# POWER_OUT.net
KiCad netlist of a schematic drawn in Altium Designer
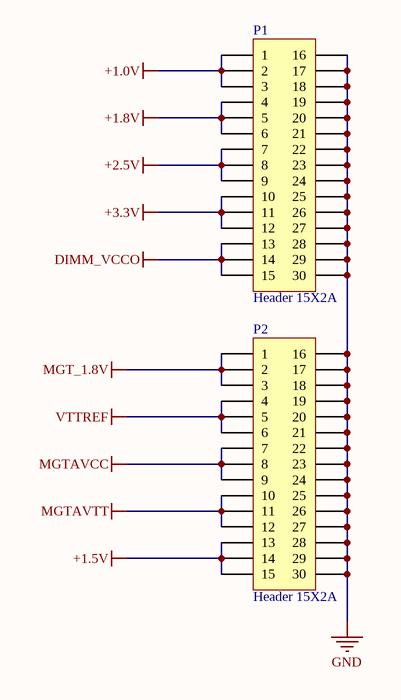
[diagram p0: POWER_OUT.SchDoc]

(export (version "E")
  (design (tool "Eeschema 10.0.6"))
  (components
    (comp (ref "P1")
      (value "Header 15X2A")
      (footprint "HDR2X15_CEN")
      (description "Header, 15-Pin, Dual row")
      (fields (field (name "PUBLISHER") "Altium Limited"))
      (libsource (lib "Miscellaneous Connectors") (part "Header 15X2A"))
    )
    (comp (ref "P2")
      (value "Header 15X2A")
      (footprint "HDR2X15_CEN")
      (description "Header, 15-Pin, Dual row")
      (fields (field (name "PUBLISHER") "Altium Limited"))
      (libsource (lib "Miscellaneous Connectors") (part "Header 15X2A"))
    )
  )
  (nets
    (net (code "1") (name "+1.0V") (class "Default")
      (node (ref "P1") (pin "1") (pinfunction "1_1") (pintype "passive"))
      (node (ref "P1") (pin "2") (pinfunction "2_2") (pintype "passive"))
      (node (ref "P1") (pin "3") (pinfunction "3_3") (pintype "passive"))
    )
    (net (code "2") (name "+1.5V") (class "Default")
      (node (ref "P2") (pin "13") (pinfunction "13_13") (pintype "passive"))
      (node (ref "P2") (pin "14") (pinfunction "14_14") (pintype "passive"))
      (node (ref "P2") (pin "15") (pinfunction "15_15") (pintype "passive"))
    )
    (net (code "3") (name "+1.8V") (class "Default")
      (node (ref "P1") (pin "4") (pinfunction "4_4") (pintype "passive"))
      (node (ref "P1") (pin "5") (pinfunction "5_5") (pintype "passive"))
      (node (ref "P1") (pin "6") (pinfunction "6_6") (pintype "passive"))
    )
    (net (code "4") (name "+2.5V") (class "Default")
      (node (ref "P1") (pin "7") (pinfunction "7_7") (pintype "passive"))
      (node (ref "P1") (pin "8") (pinfunction "8_8") (pintype "passive"))
      (node (ref "P1") (pin "9") (pinfunction "9_9") (pintype "passive"))
    )
    (net (code "5") (name "+3.3V") (class "Default")
      (node (ref "P1") (pin "10") (pinfunction "10_10") (pintype "passive"))
      (node (ref "P1") (pin "11") (pinfunction "11_11") (pintype "passive"))
      (node (ref "P1") (pin "12") (pinfunction "12_12") (pintype "passive"))
    )
    (net (code "6") (name "DIMM_VCCO") (class "Default")
      (node (ref "P1") (pin "13") (pinfunction "13_13") (pintype "passive"))
      (node (ref "P1") (pin "14") (pinfunction "14_14") (pintype "passive"))
      (node (ref "P1") (pin "15") (pinfunction "15_15") (pintype "passive"))
    )
    (net (code "7") (name "GND") (class "Default")
      (node (ref "P1") (pin "16") (pinfunction "16_16") (pintype "passive"))
      (node (ref "P1") (pin "17") (pinfunction "17_17") (pintype "passive"))
      (node (ref "P1") (pin "18") (pinfunction "18_18") (pintype "passive"))
      (node (ref "P1") (pin "19") (pinfunction "19_19") (pintype "passive"))
      (node (ref "P1") (pin "20") (pinfunction "20_20") (pintype "passive"))
      (node (ref "P1") (pin "21") (pinfunction "21_21") (pintype "passive"))
      (node (ref "P1") (pin "22") (pinfunction "22_22") (pintype "passive"))
      (node (ref "P1") (pin "23") (pinfunction "23_23") (pintype "passive"))
      (node (ref "P1") (pin "24") (pinfunction "24_24") (pintype "passive"))
      (node (ref "P1") (pin "25") (pinfunction "25_25") (pintype "passive"))
      (node (ref "P1") (pin "26") (pinfunction "26_26") (pintype "passive"))
      (node (ref "P1") (pin "27") (pinfunction "27_27") (pintype "passive"))
      (node (ref "P1") (pin "28") (pinfunction "28_28") (pintype "passive"))
      (node (ref "P1") (pin "29") (pinfunction "29_29") (pintype "passive"))
      (node (ref "P1") (pin "30") (pinfunction "30_30") (pintype "passive"))
      (node (ref "P2") (pin "16") (pinfunction "16_16") (pintype "passive"))
      (node (ref "P2") (pin "17") (pinfunction "17_17") (pintype "passive"))
      (node (ref "P2") (pin "18") (pinfunction "18_18") (pintype "passive"))
      (node (ref "P2") (pin "19") (pinfunction "19_19") (pintype "passive"))
      (node (ref "P2") (pin "20") (pinfunction "20_20") (pintype "passive"))
      (node (ref "P2") (pin "21") (pinfunction "21_21") (pintype "passive"))
      (node (ref "P2") (pin "22") (pinfunction "22_22") (pintype "passive"))
      (node (ref "P2") (pin "23") (pinfunction "23_23") (pintype "passive"))
      (node (ref "P2") (pin "24") (pinfunction "24_24") (pintype "passive"))
      (node (ref "P2") (pin "25") (pinfunction "25_25") (pintype "passive"))
      (node (ref "P2") (pin "26") (pinfunction "26_26") (pintype "passive"))
      (node (ref "P2") (pin "27") (pinfunction "27_27") (pintype "passive"))
      (node (ref "P2") (pin "28") (pinfunction "28_28") (pintype "passive"))
      (node (ref "P2") (pin "29") (pinfunction "29_29") (pintype "passive"))
      (node (ref "P2") (pin "30") (pinfunction "30_30") (pintype "passive"))
    )
    (net (code "8") (name "MGTAVCC") (class "Default")
      (node (ref "P2") (pin "7") (pinfunction "7_7") (pintype "passive"))
      (node (ref "P2") (pin "8") (pinfunction "8_8") (pintype "passive"))
      (node (ref "P2") (pin "9") (pinfunction "9_9") (pintype "passive"))
    )
    (net (code "9") (name "MGTAVTT") (class "Default")
      (node (ref "P2") (pin "10") (pinfunction "10_10") (pintype "passive"))
      (node (ref "P2") (pin "11") (pinfunction "11_11") (pintype "passive"))
      (node (ref "P2") (pin "12") (pinfunction "12_12") (pintype "passive"))
    )
    (net (code "10") (name "MGT_1.8V") (class "Default")
      (node (ref "P2") (pin "1") (pinfunction "1_1") (pintype "passive"))
      (node (ref "P2") (pin "2") (pinfunction "2_2") (pintype "passive"))
      (node (ref "P2") (pin "3") (pinfunction "3_3") (pintype "passive"))
    )
    (net (code "11") (name "VTTREF") (class "Default")
      (node (ref "P2") (pin "4") (pinfunction "4_4") (pintype "passive"))
      (node (ref "P2") (pin "5") (pinfunction "5_5") (pintype "passive"))
      (node (ref "P2") (pin "6") (pinfunction "6_6") (pintype "passive"))
    )
  )
)
